# xaef_V0.net
KiCad netlist of a schematic drawn in EAGLE
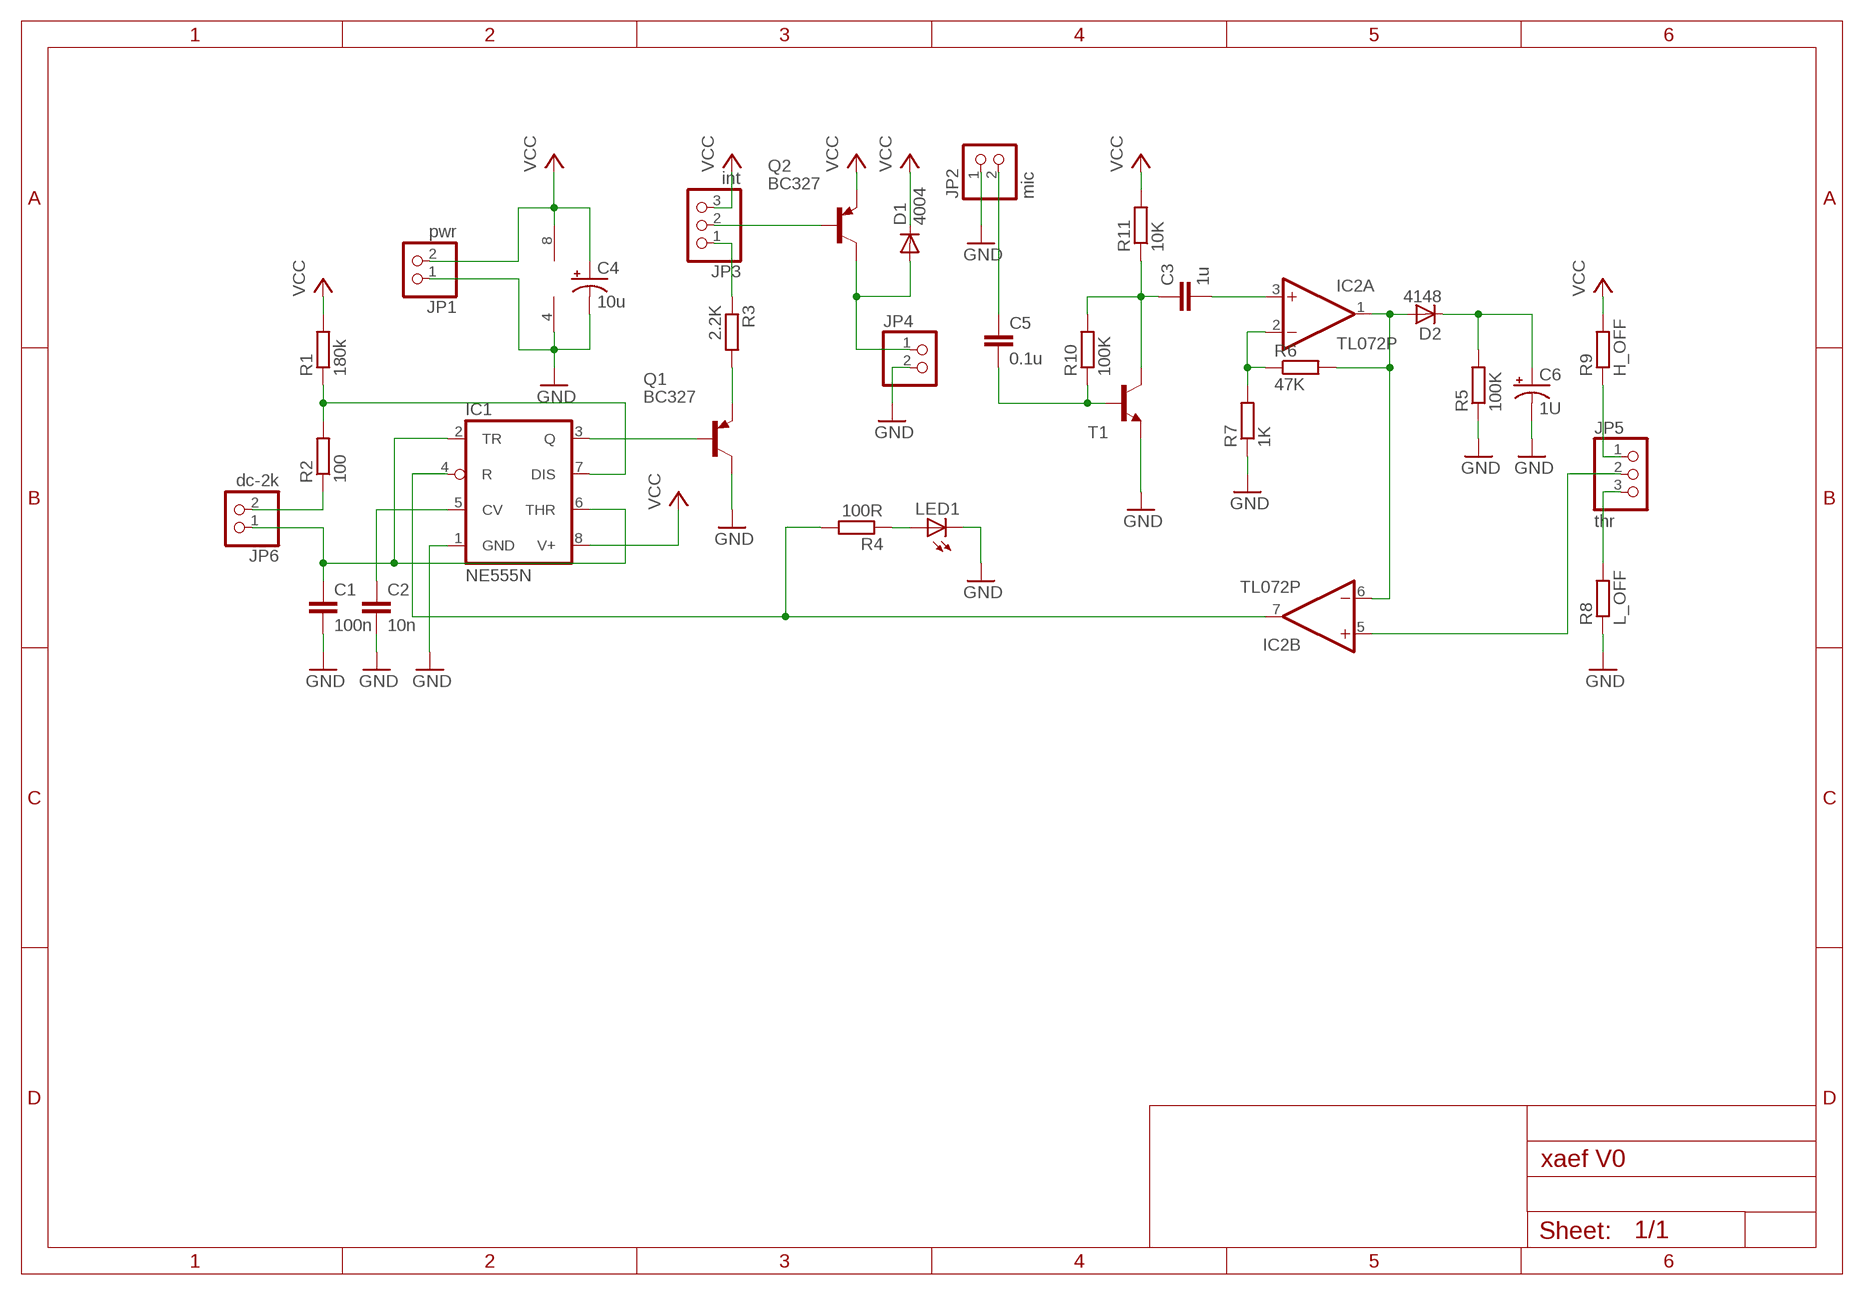
[diagram p0: schematic, sheet 1]

(export (version "E")
  (design (tool "Eeschema 10.0.6"))
  (components
    (comp (ref "C1")
      (value "100n")
      (footprint "eagle-import:C050-030X075")
      (libsource (lib "eagle-import") (part "resistor_C-EU050-030X075"))
    )
    (comp (ref "C2")
      (value "10n")
      (footprint "eagle-import:C050-030X075")
      (libsource (lib "eagle-import") (part "resistor_C-EU050-030X075"))
    )
    (comp (ref "C3")
      (value "1u")
      (footprint "eagle-import:C050-030X075")
      (libsource (lib "eagle-import") (part "resistor_C-EU050-030X075"))
    )
    (comp (ref "C4")
      (value "10u")
      (footprint "eagle-import:E3,5-8")
      (libsource (lib "eagle-import") (part "CPOL-USE3.5-8"))
    )
    (comp (ref "C5")
      (value "0.1u")
      (footprint "eagle-import:C050-025X075")
      (libsource (lib "eagle-import") (part "C-EU050-025X075"))
    )
    (comp (ref "C6")
      (value "1U")
      (footprint "eagle-import:E3,5-8")
      (libsource (lib "eagle-import") (part "CPOL-USE3.5-8"))
    )
    (comp (ref "D1")
      (value "4004")
      (footprint "eagle-import:D-2.5")
      (libsource (lib "eagle-import") (part "DIODE-D-2.5"))
    )
    (comp (ref "D2")
      (value "4148")
      (footprint "eagle-import:DIODE_DO35-7")
      (libsource (lib "eagle-import") (part "DIODE_E-DO35-7"))
    )
    (comp (ref "IC1")
      (value "NE555N")
      (footprint "eagle-import:DIL08-ROUND")
      (libsource (lib "eagle-import") (part "555NNE"))
    )
    (comp (ref "IC2")
      (value "TL072P")
      (footprint "eagle-import:DIL08")
      (libsource (lib "eagle-import") (part "TL072P"))
    )
    (comp (ref "JP1")
      (value "pwr")
      (footprint "eagle-import:1X02")
      (libsource (lib "eagle-import") (part "PINHD-1X2"))
    )
    (comp (ref "JP2")
      (value "mic")
      (footprint "eagle-import:1X02")
      (libsource (lib "eagle-import") (part "PINHD-1X2"))
    )
    (comp (ref "JP3")
      (value "int")
      (footprint "eagle-import:1X03")
      (libsource (lib "eagle-import") (part "PINHD-1X3"))
    )
    (comp (ref "JP4")
      (value "PINHD-1X2")
      (footprint "eagle-import:1X02")
      (libsource (lib "eagle-import") (part "PINHD-1X2"))
    )
    (comp (ref "JP5")
      (value "thr")
      (footprint "eagle-import:1X03")
      (libsource (lib "eagle-import") (part "PINHD-1X3"))
    )
    (comp (ref "JP6")
      (value "dc-2k")
      (footprint "eagle-import:1X02")
      (libsource (lib "eagle-import") (part "PINHD-1X2"))
    )
    (comp (ref "LED1")
      (value "LED5MM")
      (footprint "eagle-import:LED5MM")
      (libsource (lib "eagle-import") (part "LED5MM"))
    )
    (comp (ref "Q1")
      (value "BC327")
      (footprint "eagle-import:TO92-EBC")
      (libsource (lib "eagle-import") (part "BC327-25"))
    )
    (comp (ref "Q2")
      (value "BC327")
      (footprint "eagle-import:TO92-EBC")
      (libsource (lib "eagle-import") (part "BC327-25"))
    )
    (comp (ref "R1")
      (value "180k")
      (footprint "eagle-import:0207_2V")
      (libsource (lib "eagle-import") (part "R-EU_0207/2V"))
    )
    (comp (ref "R2")
      (value "100")
      (footprint "eagle-import:0207_2V")
      (libsource (lib "eagle-import") (part "R-EU_0207/2V"))
    )
    (comp (ref "R3")
      (value "2.2K")
      (footprint "eagle-import:0207_2V")
      (libsource (lib "eagle-import") (part "R-EU_0207/2V"))
    )
    (comp (ref "R4")
      (value "100R")
      (footprint "eagle-import:0207_2V")
      (libsource (lib "eagle-import") (part "R-EU_0207/2V"))
    )
    (comp (ref "R5")
      (value "100K")
      (footprint "eagle-import:0207_2V")
      (libsource (lib "eagle-import") (part "R-EU_0207/2V"))
    )
    (comp (ref "R6")
      (value "47K")
      (footprint "eagle-import:0207_2V")
      (libsource (lib "eagle-import") (part "R-EU_0207/2V"))
    )
    (comp (ref "R7")
      (value "1K")
      (footprint "eagle-import:0207_2V")
      (libsource (lib "eagle-import") (part "R-EU_0207/2V"))
    )
    (comp (ref "R8")
      (value "L_OFF")
      (footprint "eagle-import:0207_2V")
      (libsource (lib "eagle-import") (part "R-EU_0207/2V"))
    )
    (comp (ref "R9")
      (value "H_OFF")
      (footprint "eagle-import:0207_2V")
      (libsource (lib "eagle-import") (part "R-EU_0207/2V"))
    )
    (comp (ref "R10")
      (value "100K")
      (footprint "eagle-import:0207_2V")
      (libsource (lib "eagle-import") (part "R-EU_0207/2V"))
    )
    (comp (ref "R11")
      (value "10K")
      (footprint "eagle-import:0207_2V")
      (libsource (lib "eagle-import") (part "R-EU_0207/2V"))
    )
    (comp (ref "T1")
      (value "2N3904-NPN-TO92-EBC")
      (footprint "eagle-import:TO92-EBC")
      (libsource (lib "eagle-import") (part "-NPN-TO92-EBC2N3904"))
    )
  )
  (nets
    (net (code "1") (name "GND") (class "Default")
      (node (ref "C1") (pin "2") (pinfunction "2_2") (pintype "passive"))
      (node (ref "C2") (pin "2") (pinfunction "2_2") (pintype "passive"))
      (node (ref "C4") (pin "-") (pinfunction "-_-") (pintype "passive"))
      (node (ref "C6") (pin "-") (pinfunction "-_-") (pintype "passive"))
      (node (ref "IC1") (pin "1") (pinfunction "GND_1") (pintype "power_in"))
      (node (ref "IC2") (pin "4") (pinfunction "V-_4") (pintype "power_in"))
      (node (ref "JP1") (pin "1") (pinfunction "1_1") (pintype "passive"))
      (node (ref "JP2") (pin "1") (pinfunction "1_1") (pintype "passive"))
      (node (ref "JP4") (pin "2") (pinfunction "2_2") (pintype "passive"))
      (node (ref "LED1") (pin "K") (pinfunction "C_K") (pintype "passive"))
      (node (ref "Q1") (pin "C") (pinfunction "C_C") (pintype "passive"))
      (node (ref "R5") (pin "1") (pinfunction "1_1") (pintype "passive"))
      (node (ref "R7") (pin "1") (pinfunction "1_1") (pintype "passive"))
      (node (ref "R8") (pin "1") (pinfunction "1_1") (pintype "passive"))
      (node (ref "T1") (pin "E") (pinfunction "E_E") (pintype "passive"))
    )
    (net (code "2") (name "Net-(C3-Pad1)") (class "Default")
      (node (ref "C3") (pin "1") (pinfunction "1_1") (pintype "passive"))
      (node (ref "R10") (pin "2") (pinfunction "2_2") (pintype "passive"))
      (node (ref "R11") (pin "1") (pinfunction "1_1") (pintype "passive"))
      (node (ref "T1") (pin "C") (pinfunction "C_C") (pintype "passive"))
    )
    (net (code "3") (name "Net-(C5-Pad1)") (class "Default")
      (node (ref "C5") (pin "1") (pinfunction "1_1") (pintype "passive"))
      (node (ref "JP2") (pin "2") (pinfunction "2_2") (pintype "passive"))
    )
    (net (code "4") (name "Net-(C5-Pad2)") (class "Default")
      (node (ref "C5") (pin "2") (pinfunction "2_2") (pintype "passive"))
      (node (ref "R10") (pin "1") (pinfunction "1_1") (pintype "passive"))
      (node (ref "T1") (pin "B") (pinfunction "B_B") (pintype "passive"))
    )
    (net (code "5") (name "Net-(D1-PadA)") (class "Default")
      (node (ref "D1") (pin "A") (pinfunction "A_A") (pintype "passive"))
      (node (ref "JP4") (pin "1") (pinfunction "1_1") (pintype "passive"))
      (node (ref "Q2") (pin "C") (pinfunction "C_C") (pintype "passive"))
    )
    (net (code "6") (name "Net-(D2-A)") (class "Default")
      (node (ref "C6") (pin "+") (pinfunction "+_+") (pintype "passive"))
      (node (ref "D2") (pin "C") (pinfunction "A_C") (pintype "passive"))
      (node (ref "R5") (pin "2") (pinfunction "2_2") (pintype "passive"))
    )
    (net (code "7") (name "Net-(D2-C)") (class "Default")
      (node (ref "D2") (pin "A") (pinfunction "C_A") (pintype "passive"))
      (node (ref "IC2") (pin "1") (pinfunction "OUT_1") (pintype "output"))
      (node (ref "IC2") (pin "6") (pinfunction "-IN_6") (pintype "input"))
      (node (ref "R6") (pin "2") (pinfunction "2_2") (pintype "passive"))
    )
    (net (code "8") (name "Net-(IC1-CV)") (class "Default")
      (node (ref "C2") (pin "1") (pinfunction "1_1") (pintype "passive"))
      (node (ref "IC1") (pin "5") (pinfunction "CV_5") (pintype "input"))
    )
    (net (code "9") (name "Net-(IC1-DIS)") (class "Default")
      (node (ref "IC1") (pin "7") (pinfunction "DIS_7") (pintype "input"))
      (node (ref "R1") (pin "1") (pinfunction "1_1") (pintype "passive"))
      (node (ref "R2") (pin "2") (pinfunction "2_2") (pintype "passive"))
    )
    (net (code "10") (name "Net-(IC1-Q)") (class "Default")
      (node (ref "IC1") (pin "3") (pinfunction "Q_3") (pintype "output"))
      (node (ref "Q1") (pin "B") (pinfunction "B_B") (pintype "passive"))
    )
    (net (code "11") (name "Net-(IC1-R)") (class "Default")
      (node (ref "IC1") (pin "4") (pinfunction "R_4") (pintype "input"))
      (node (ref "IC2") (pin "7") (pinfunction "OUT_7") (pintype "output"))
      (node (ref "R4") (pin "2") (pinfunction "2_2") (pintype "passive"))
    )
    (net (code "12") (name "Net-(IC1-THR)") (class "Default")
      (node (ref "C1") (pin "1") (pinfunction "1_1") (pintype "passive"))
      (node (ref "IC1") (pin "2") (pinfunction "TR_2") (pintype "input"))
      (node (ref "IC1") (pin "6") (pinfunction "THR_6") (pintype "input"))
      (node (ref "JP6") (pin "1") (pinfunction "1_1") (pintype "passive"))
    )
    (net (code "13") (name "Net-(IC2A-+IN)") (class "Default")
      (node (ref "C3") (pin "2") (pinfunction "2_2") (pintype "passive"))
      (node (ref "IC2") (pin "3") (pinfunction "+IN_3") (pintype "input"))
    )
    (net (code "14") (name "Net-(IC2A--IN)") (class "Default")
      (node (ref "IC2") (pin "2") (pinfunction "-IN_2") (pintype "input"))
      (node (ref "R6") (pin "1") (pinfunction "1_1") (pintype "passive"))
      (node (ref "R7") (pin "2") (pinfunction "2_2") (pintype "passive"))
    )
    (net (code "15") (name "Net-(IC2B-+IN)") (class "Default")
      (node (ref "IC2") (pin "5") (pinfunction "+IN_5") (pintype "input"))
      (node (ref "JP5") (pin "2") (pinfunction "2_2") (pintype "passive"))
    )
    (net (code "16") (name "Net-(JP3-Pad1)") (class "Default")
      (node (ref "JP3") (pin "1") (pinfunction "1_1") (pintype "passive"))
      (node (ref "R3") (pin "1") (pinfunction "1_1") (pintype "passive"))
    )
    (net (code "17") (name "Net-(JP3-Pad2)") (class "Default")
      (node (ref "JP3") (pin "2") (pinfunction "2_2") (pintype "passive"))
      (node (ref "Q2") (pin "B") (pinfunction "B_B") (pintype "passive"))
    )
    (net (code "18") (name "Net-(JP5-Pad1)") (class "Default")
      (node (ref "JP5") (pin "1") (pinfunction "1_1") (pintype "passive"))
      (node (ref "R9") (pin "1") (pinfunction "1_1") (pintype "passive"))
    )
    (net (code "19") (name "Net-(JP5-Pad3)") (class "Default")
      (node (ref "JP5") (pin "3") (pinfunction "3_3") (pintype "passive"))
      (node (ref "R8") (pin "2") (pinfunction "2_2") (pintype "passive"))
    )
    (net (code "20") (name "Net-(JP6-Pad2)") (class "Default")
      (node (ref "JP6") (pin "2") (pinfunction "2_2") (pintype "passive"))
      (node (ref "R2") (pin "1") (pinfunction "1_1") (pintype "passive"))
    )
    (net (code "21") (name "Net-(LED1-PadA)") (class "Default")
      (node (ref "LED1") (pin "A") (pinfunction "A_A") (pintype "passive"))
      (node (ref "R4") (pin "1") (pinfunction "1_1") (pintype "passive"))
    )
    (net (code "22") (name "Net-(Q1-PadE)") (class "Default")
      (node (ref "Q1") (pin "E") (pinfunction "E_E") (pintype "passive"))
      (node (ref "R3") (pin "2") (pinfunction "2_2") (pintype "passive"))
    )
    (net (code "23") (name "VCC") (class "Default")
      (node (ref "C4") (pin "+") (pinfunction "+_+") (pintype "passive"))
      (node (ref "D1") (pin "C") (pinfunction "C_C") (pintype "passive"))
      (node (ref "IC1") (pin "8") (pinfunction "V+_8") (pintype "power_in"))
      (node (ref "IC2") (pin "8") (pinfunction "V+_8") (pintype "power_in"))
      (node (ref "JP1") (pin "2") (pinfunction "2_2") (pintype "passive"))
      (node (ref "JP3") (pin "3") (pinfunction "3_3") (pintype "passive"))
      (node (ref "Q2") (pin "E") (pinfunction "E_E") (pintype "passive"))
      (node (ref "R1") (pin "2") (pinfunction "2_2") (pintype "passive"))
      (node (ref "R11") (pin "2") (pinfunction "2_2") (pintype "passive"))
      (node (ref "R9") (pin "2") (pinfunction "2_2") (pintype "passive"))
    )
  )
)
